# UniversalFullBridge.net
KiCad netlist of a schematic drawn in Altium Designer
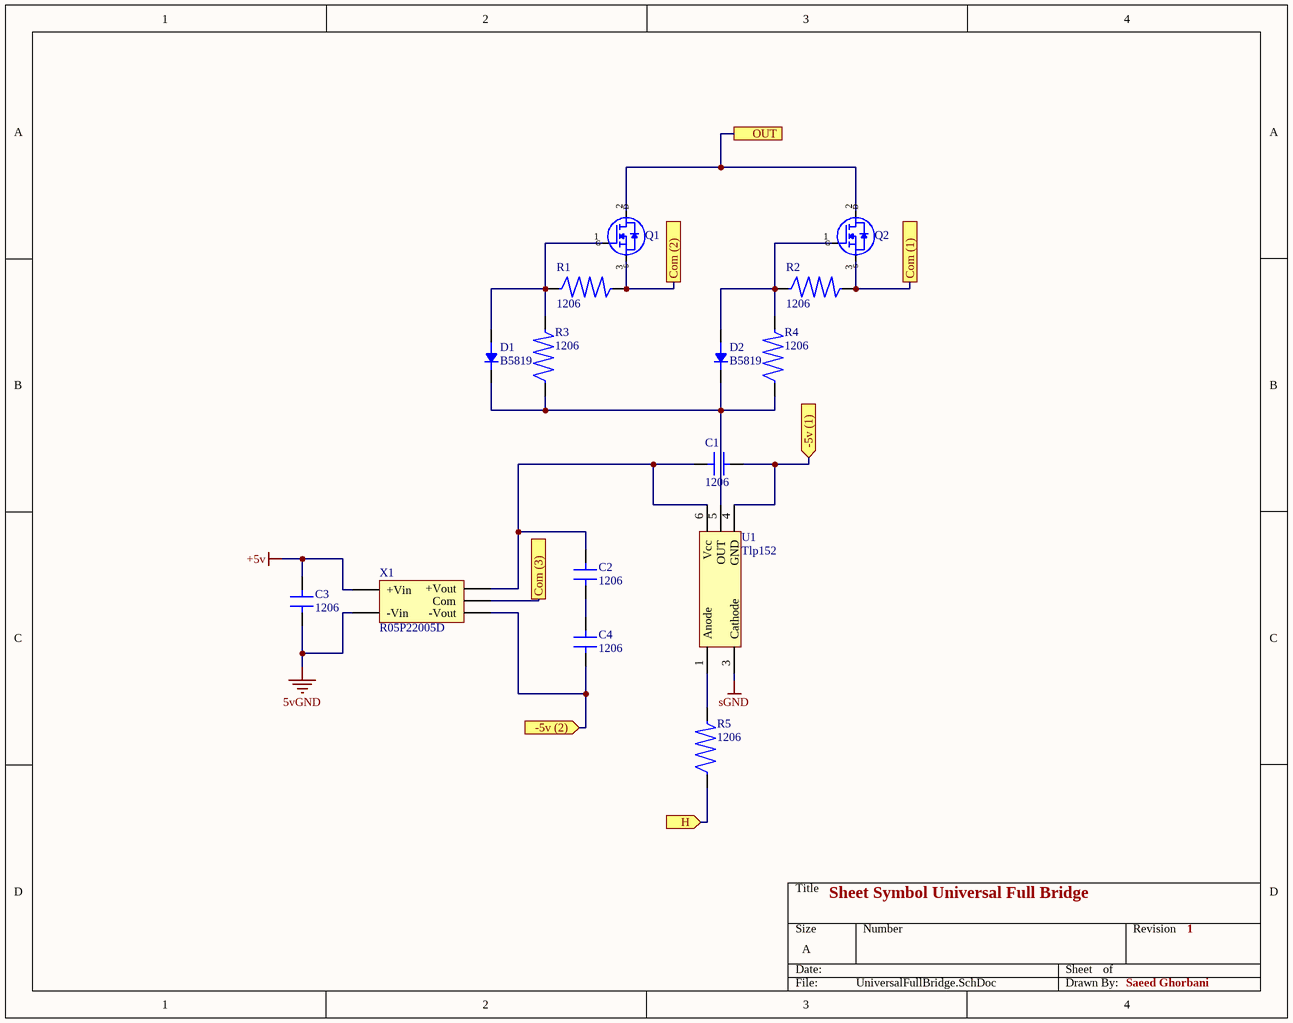
[diagram p0: UniversalFullBridge.SchDoc]

(export (version "E")
  (design (tool "Eeschema 10.0.6"))
  (components
    (comp (ref "C1") (value "1206") (libsource (lib "UniversalFullBridge") (part "Capcitor (1206)")))
    (comp (ref "C2") (value "1206") (libsource (lib "UniversalFullBridge") (part "Capcitor (1206)")))
    (comp (ref "C3") (value "1206") (libsource (lib "UniversalFullBridge") (part "Capcitor (1206)")))
    (comp (ref "C4") (value "1206") (libsource (lib "UniversalFullBridge") (part "Capcitor (1206)")))
    (comp (ref "D1") (value "B5819") (libsource (lib "UniversalFullBridge") (part "Diode")))
    (comp (ref "D2") (value "B5819") (libsource (lib "UniversalFullBridge") (part "Diode")))
    (comp (ref "Q1") (value "To263 Mosfet") (libsource (lib "UniversalFullBridge") (part "To263 Mosfet")))
    (comp (ref "Q2") (value "To263 Mosfet") (libsource (lib "UniversalFullBridge") (part "To263 Mosfet")))
    (comp (ref "R1") (value "1206") (libsource (lib "UniversalFullBridge") (part "Resistor (1206)")))
    (comp (ref "R2") (value "1206") (libsource (lib "UniversalFullBridge") (part "Resistor (1206)")))
    (comp (ref "R3") (value "1206") (libsource (lib "UniversalFullBridge") (part "Resistor (1206)")))
    (comp (ref "R4") (value "1206") (libsource (lib "UniversalFullBridge") (part "Resistor (1206)")))
    (comp (ref "R5") (value "1206") (libsource (lib "UniversalFullBridge") (part "Resistor (1206)")))
    (comp (ref "U1") (value "Tlp152") (libsource (lib "UniversalFullBridge") (part "Tlp152")))
    (comp (ref "X1") (value "R05P22005D") (libsource (lib "UniversalFullBridge") (part "DC_DC Converter")))
  )
  (nets
    (net (code "1") (name "+5v") (class "Default")
      (node (ref "C3") (pin "2") (pinfunction "2_2") (pintype "passive"))
      (node (ref "X1") (pin "1") (pinfunction "+Vin_1") (pintype "passive"))
    )
    (net (code "2") (name "/-5v (1)") (class "Default")
      (node (ref "C1") (pin "2") (pinfunction "2_2") (pintype "passive"))
      (node (ref "U1") (pin "4") (pinfunction "GND_4") (pintype "passive"))
    )
    (net (code "3") (name "/-5v (2)") (class "Default")
      (node (ref "C4") (pin "1") (pinfunction "1_1") (pintype "passive"))
      (node (ref "X1") (pin "5") (pinfunction "-Vout_5") (pintype "passive"))
    )
    (net (code "4") (name "/Com (1)") (class "Default")
      (node (ref "Q2") (pin "3") (pinfunction "S_3") (pintype "passive"))
      (node (ref "R2") (pin "2") (pinfunction "2_2") (pintype "passive"))
    )
    (net (code "5") (name "/Com (2)") (class "Default")
      (node (ref "Q1") (pin "3") (pinfunction "S_3") (pintype "passive"))
      (node (ref "R1") (pin "2") (pinfunction "2_2") (pintype "passive"))
    )
    (net (code "6") (name "/Com (3)") (class "Default")
      (node (ref "X1") (pin "6") (pinfunction "Com_6") (pintype "passive"))
    )
    (net (code "7") (name "/H") (class "Default")
      (node (ref "R5") (pin "1") (pinfunction "1_1") (pintype "passive"))
    )
    (net (code "8") (name "/OUT") (class "Default")
      (node (ref "Q1") (pin "2") (pinfunction "D_2") (pintype "passive"))
      (node (ref "Q2") (pin "2") (pinfunction "D_2") (pintype "passive"))
    )
    (net (code "9") (name "5vGND") (class "Default")
      (node (ref "C3") (pin "1") (pinfunction "1_1") (pintype "passive"))
      (node (ref "X1") (pin "2") (pinfunction "-Vin_2") (pintype "passive"))
    )
    (net (code "10") (name "Net-(C2-Pad1)") (class "Default")
      (node (ref "C2") (pin "1") (pinfunction "1_1") (pintype "passive"))
      (node (ref "C4") (pin "2") (pinfunction "2_2") (pintype "passive"))
    )
    (net (code "11") (name "Net-(D1-Anode)") (class "Default")
      (node (ref "D1") (pin "1") (pinfunction "Anode_1") (pintype "passive"))
      (node (ref "Q1") (pin "1") (pinfunction "G_1") (pintype "passive"))
      (node (ref "R1") (pin "1") (pinfunction "1_1") (pintype "passive"))
      (node (ref "R3") (pin "2") (pinfunction "2_2") (pintype "passive"))
    )
    (net (code "12") (name "Net-(D1-Cathode)") (class "Default")
      (node (ref "D1") (pin "2") (pinfunction "Cathode_2") (pintype "passive"))
      (node (ref "D2") (pin "2") (pinfunction "Cathode_2") (pintype "passive"))
      (node (ref "R3") (pin "1") (pinfunction "1_1") (pintype "passive"))
      (node (ref "R4") (pin "1") (pinfunction "1_1") (pintype "passive"))
      (node (ref "U1") (pin "5") (pinfunction "OUT_5") (pintype "passive"))
    )
    (net (code "13") (name "Net-(D2-Anode)") (class "Default")
      (node (ref "D2") (pin "1") (pinfunction "Anode_1") (pintype "passive"))
      (node (ref "Q2") (pin "1") (pinfunction "G_1") (pintype "passive"))
      (node (ref "R2") (pin "1") (pinfunction "1_1") (pintype "passive"))
      (node (ref "R4") (pin "2") (pinfunction "2_2") (pintype "passive"))
    )
    (net (code "14") (name "Net-(U1-Anode)") (class "Default")
      (node (ref "R5") (pin "2") (pinfunction "2_2") (pintype "passive"))
      (node (ref "U1") (pin "1") (pinfunction "Anode_1") (pintype "passive"))
    )
    (net (code "15") (name "Net-(U1-Vcc)") (class "Default")
      (node (ref "C1") (pin "1") (pinfunction "1_1") (pintype "passive"))
      (node (ref "C2") (pin "2") (pinfunction "2_2") (pintype "passive"))
      (node (ref "U1") (pin "6") (pinfunction "Vcc_6") (pintype "passive"))
      (node (ref "X1") (pin "7") (pinfunction "+Vout_7") (pintype "passive"))
    )
    (net (code "16") (name "sGND") (class "Default")
      (node (ref "U1") (pin "3") (pinfunction "Cathode_3") (pintype "passive"))
    )
  )
)
